# rys_PCB.net
KiCad netlist of a schematic drawn in Altium Designer
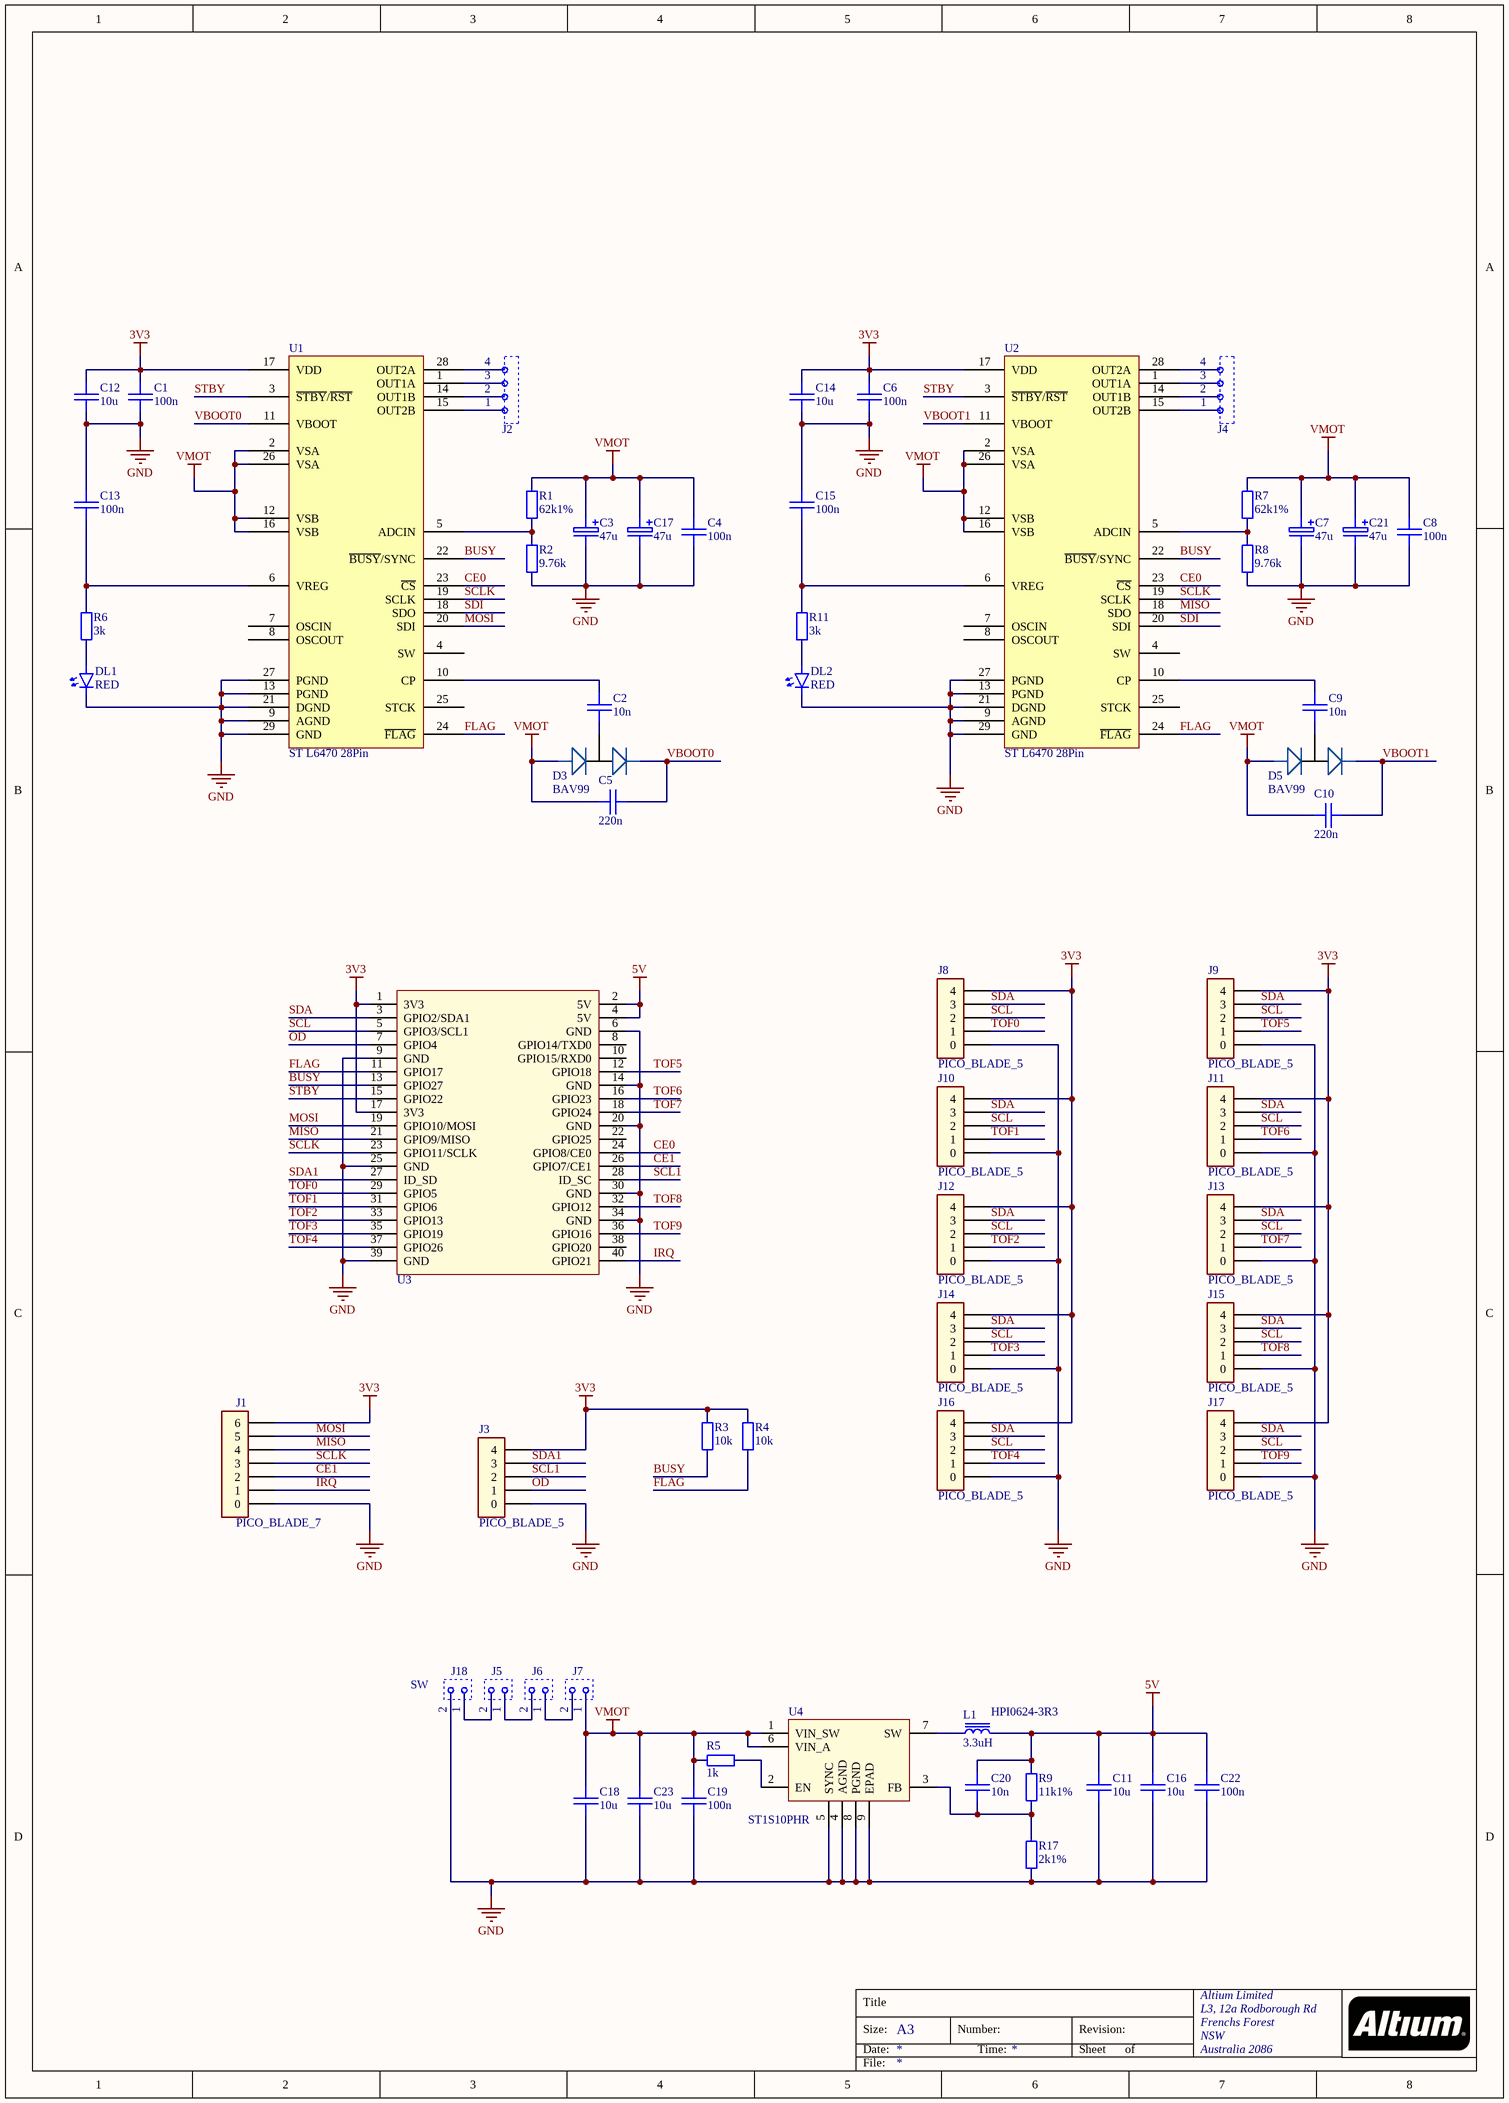
[diagram p0: rys_PCB.SchDoc]

(export (version "E")
  (design (tool "Eeschema 10.0.6"))
  (components
    (comp (ref "C1")
      (value "100n")
      (footprint "Other-Discrete:0603")
      (description "Ceramic Capacitor")
      (libsource (lib "Disc-Other") (part "C_CER"))
    )
    (comp (ref "C2")
      (value "10n")
      (footprint "Other-Discrete:0603")
      (description "Ceramic Capacitor")
      (libsource (lib "Disc-Other") (part "C_CER"))
    )
    (comp (ref "C3")
      (value "47u")
      (footprint "_C_TAN_D")
      (description "Tantalum Capacitor")
      (libsource (lib "Disc-Other") (part "C_TAN"))
    )
    (comp (ref "C4")
      (value "100n")
      (footprint "Other-Discrete:0603")
      (description "Ceramic Capacitor")
      (libsource (lib "Disc-Other") (part "C_CER"))
    )
    (comp (ref "C5")
      (value "220n")
      (footprint "Other-Discrete:0805")
      (description "Ceramic Capacitor")
      (libsource (lib "Disc-Other") (part "C_CER"))
    )
    (comp (ref "C6")
      (value "100n")
      (footprint "Other-Discrete:0603")
      (description "Ceramic Capacitor")
      (libsource (lib "Disc-Other") (part "C_CER"))
    )
    (comp (ref "C7")
      (value "47u")
      (footprint "_C_TAN_D")
      (description "Tantalum Capacitor")
      (libsource (lib "Disc-Other") (part "C_TAN"))
    )
    (comp (ref "C8")
      (value "100n")
      (footprint "Other-Discrete:0603")
      (description "Ceramic Capacitor")
      (libsource (lib "Disc-Other") (part "C_CER"))
    )
    (comp (ref "C9")
      (value "10n")
      (footprint "Other-Discrete:0603")
      (description "Ceramic Capacitor")
      (libsource (lib "Disc-Other") (part "C_CER"))
    )
    (comp (ref "C10")
      (value "220n")
      (footprint "Other-Discrete:0805")
      (description "Ceramic Capacitor")
      (libsource (lib "Disc-Other") (part "C_CER"))
    )
    (comp (ref "C11")
      (value "10u")
      (footprint "Other-Discrete:1210_C")
      (description "Ceramic Capacitor")
      (libsource (lib "Disc-Other") (part "C_CER"))
    )
    (comp (ref "C12")
      (value "10u")
      (footprint "Other-Discrete:1206_C")
      (description "Ceramic Capacitor")
      (libsource (lib "Disc-Other") (part "C_CER"))
    )
    (comp (ref "C13")
      (value "100n")
      (footprint "Other-Discrete:0603")
      (description "Ceramic Capacitor")
      (libsource (lib "Disc-Other") (part "C_CER"))
    )
    (comp (ref "C14")
      (value "10u")
      (footprint "Other-Discrete:1206_C")
      (description "Ceramic Capacitor")
      (libsource (lib "Disc-Other") (part "C_CER"))
    )
    (comp (ref "C15")
      (value "100n")
      (footprint "Other-Discrete:0603")
      (description "Ceramic Capacitor")
      (libsource (lib "Disc-Other") (part "C_CER"))
    )
    (comp (ref "C16")
      (value "10u")
      (footprint "Other-Discrete:1210_C")
      (description "Ceramic Capacitor")
      (libsource (lib "Disc-Other") (part "C_CER"))
    )
    (comp (ref "C17")
      (value "47u")
      (footprint "_C_TAN_D")
      (description "Tantalum Capacitor")
      (libsource (lib "Disc-Other") (part "C_TAN"))
    )
    (comp (ref "C18")
      (value "10u")
      (footprint "Other-Discrete:1210_C")
      (description "Ceramic Capacitor")
      (libsource (lib "Disc-Other") (part "C_CER"))
    )
    (comp (ref "C19")
      (value "100n")
      (footprint "Other-Discrete:0603")
      (description "Ceramic Capacitor")
      (libsource (lib "Disc-Other") (part "C_CER"))
    )
    (comp (ref "C20")
      (value "10n")
      (footprint "Other-Discrete:0603")
      (description "Ceramic Capacitor")
      (libsource (lib "Disc-Other") (part "C_CER"))
    )
    (comp (ref "C21")
      (value "47u")
      (footprint "_C_TAN_D")
      (description "Tantalum Capacitor")
      (libsource (lib "Disc-Other") (part "C_TAN"))
    )
    (comp (ref "C22")
      (value "100n")
      (footprint "Other-Discrete:0603")
      (description "Ceramic Capacitor")
      (libsource (lib "Disc-Other") (part "C_CER"))
    )
    (comp (ref "C23")
      (value "10u")
      (footprint "Other-Discrete:1210_C")
      (description "Ceramic Capacitor")
      (libsource (lib "Disc-Other") (part "C_CER"))
    )
    (comp (ref "D3")
      (value "BAV99")
      (footprint "SOT-23")
      (description "Charge pump diode")
      (libsource (lib "rys_component_lib") (part "BAV99"))
    )
    (comp (ref "D5")
      (value "BAV99")
      (footprint "SOT-23")
      (description "Charge pump diode")
      (libsource (lib "rys_component_lib") (part "BAV99"))
    )
    (comp (ref "DL1")
      (value "RED")
      (footprint "Other-Discrete:0805_LED")
      (description "Light Emitting Diode")
      (libsource (lib "Disc-Opto") (part "LED1"))
    )
    (comp (ref "DL2")
      (value "RED")
      (footprint "Other-Discrete:0805_LED")
      (description "Light Emitting Diode")
      (libsource (lib "Disc-Opto") (part "LED1"))
    )
    (comp (ref "J1")
      (value "PICO_BLADE_7")
      (footprint "PicoBlade_THT_1x7_HEADER")
      (description "1x7 header")
      (libsource (lib "rys_component_lib") (part "PICO_BLADE_7"))
    )
    (comp (ref "J2")
      (value "Molex Microfit")
      (footprint "MICROFIT 4x1 Vertical")
      (libsource (lib "rys_component_lib") (part "Microfit 1x4"))
    )
    (comp (ref "J3")
      (value "PICO_BLADE_5")
      (footprint "PicoBlade_THT_1x5_HEADER")
      (description "1x5 header")
      (libsource (lib "rys_component_lib") (part "PICO_BLADE_5"))
    )
    (comp (ref "J4")
      (value "Molex Microfit")
      (footprint "MICROFIT 4x1 Vertical")
      (libsource (lib "rys_component_lib") (part "Microfit 1x4"))
    )
    (comp (ref "J5")
      (value "Molex Microfit")
      (footprint "MicroFit:MICROFIT 1x2 Vertical")
      (libsource (lib "Connectors") (part "Microfit 2x1"))
    )
    (comp (ref "J6")
      (value "Molex Microfit")
      (footprint "MicroFit:MICROFIT 1x2 Vertical")
      (libsource (lib "Connectors") (part "Microfit 2x1"))
    )
    (comp (ref "J7")
      (value "Molex Microfit")
      (footprint "MicroFit:MICROFIT 1x2 Vertical")
      (libsource (lib "Connectors") (part "Microfit 2x1"))
    )
    (comp (ref "J8")
      (value "PICO_BLADE_5")
      (footprint "PicoBlade_THT_1x5_HEADER")
      (description "1x5 header")
      (libsource (lib "rys_component_lib") (part "PICO_BLADE_5"))
    )
    (comp (ref "J9")
      (value "PICO_BLADE_5")
      (footprint "PicoBlade_THT_1x5_HEADER")
      (description "1x5 header")
      (libsource (lib "rys_component_lib") (part "PICO_BLADE_5"))
    )
    (comp (ref "J10")
      (value "PICO_BLADE_5")
      (footprint "PicoBlade_THT_1x5_HEADER")
      (description "1x5 header")
      (libsource (lib "rys_component_lib") (part "PICO_BLADE_5"))
    )
    (comp (ref "J11")
      (value "PICO_BLADE_5")
      (footprint "PicoBlade_THT_1x5_HEADER")
      (description "1x5 header")
      (libsource (lib "rys_component_lib") (part "PICO_BLADE_5"))
    )
    (comp (ref "J12")
      (value "PICO_BLADE_5")
      (footprint "PicoBlade_THT_1x5_HEADER")
      (description "1x5 header")
      (libsource (lib "rys_component_lib") (part "PICO_BLADE_5"))
    )
    (comp (ref "J13")
      (value "PICO_BLADE_5")
      (footprint "PicoBlade_THT_1x5_HEADER")
      (description "1x5 header")
      (libsource (lib "rys_component_lib") (part "PICO_BLADE_5"))
    )
    (comp (ref "J14")
      (value "PICO_BLADE_5")
      (footprint "PicoBlade_THT_1x5_HEADER")
      (description "1x5 header")
      (libsource (lib "rys_component_lib") (part "PICO_BLADE_5"))
    )
    (comp (ref "J15")
      (value "PICO_BLADE_5")
      (footprint "PicoBlade_THT_1x5_HEADER")
      (description "1x5 header")
      (libsource (lib "rys_component_lib") (part "PICO_BLADE_5"))
    )
    (comp (ref "J16")
      (value "PICO_BLADE_5")
      (footprint "PicoBlade_THT_1x5_HEADER")
      (description "1x5 header")
      (libsource (lib "rys_component_lib") (part "PICO_BLADE_5"))
    )
    (comp (ref "J17")
      (value "PICO_BLADE_5")
      (footprint "PicoBlade_THT_1x5_HEADER")
      (description "1x5 header")
      (libsource (lib "rys_component_lib") (part "PICO_BLADE_5"))
    )
    (comp (ref "J18")
      (value "Molex Microfit")
      (footprint "MicroFit:MICROFIT 1x2 Vertical")
      (libsource (lib "Connectors") (part "Microfit 2x1"))
    )
    (comp (ref "L1")
      (value "3.3uH")
      (footprint "L_HPI0624")
      (description "Inductor")
      (fields (field (name "SYMBOL") "HPI0624-3R3"))
      (libsource (lib "rys_component_lib") (part "L_IND_HPI0624-3R3"))
    )
    (comp (ref "R1")
      (value "62k1%")
      (footprint "Other-Discrete:0603_R")
      (description "Resistor")
      (libsource (lib "Disc-Other") (part "R"))
    )
    (comp (ref "R2")
      (value "9.76k")
      (footprint "Other-Discrete:0603_R")
      (description "Resistor")
      (libsource (lib "Disc-Other") (part "R"))
    )
    (comp (ref "R3")
      (value "10k")
      (footprint "Other-Discrete:0603_R")
      (description "Resistor")
      (libsource (lib "Disc-Other") (part "R"))
    )
    (comp (ref "R4")
      (value "10k")
      (footprint "Other-Discrete:0603_R")
      (description "Resistor")
      (libsource (lib "Disc-Other") (part "R"))
    )
    (comp (ref "R5")
      (value "1k")
      (footprint "Other-Discrete:0603_R")
      (description "Resistor")
      (libsource (lib "Disc-Other") (part "R"))
    )
    (comp (ref "R6")
      (value "3k")
      (footprint "Other-Discrete:0603_R")
      (description "Resistor")
      (libsource (lib "Disc-Other") (part "R"))
    )
    (comp (ref "R7")
      (value "62k1%")
      (footprint "Other-Discrete:0603_R")
      (description "Resistor")
      (libsource (lib "Disc-Other") (part "R"))
    )
    (comp (ref "R8")
      (value "9.76k")
      (footprint "Other-Discrete:0603_R")
      (description "Resistor")
      (libsource (lib "Disc-Other") (part "R"))
    )
    (comp (ref "R9")
      (value "11k1%")
      (footprint "Other-Discrete:0603_R")
      (description "Resistor")
      (libsource (lib "Disc-Other") (part "R"))
    )
    (comp (ref "R11")
      (value "3k")
      (footprint "Other-Discrete:0603_R")
      (description "Resistor")
      (libsource (lib "Disc-Other") (part "R"))
    )
    (comp (ref "R17")
      (value "2k1%")
      (footprint "Other-Discrete:0603_R")
      (description "Resistor")
      (libsource (lib "Disc-Other") (part "R"))
    )
    (comp (ref "U1")
      (value "ST L6470 28Pin")
      (footprint "ST HTSSOP-28")
      (description "SPI stepper driver")
      (libsource (lib "rys_component_lib") (part "ST L6470 28Pin"))
    )
    (comp (ref "U2")
      (value "ST L6470 28Pin")
      (footprint "ST HTSSOP-28")
      (description "SPI stepper driver")
      (libsource (lib "rys_component_lib") (part "ST L6470 28Pin"))
    )
    (comp (ref "U3")
      (value "RaspberryPi_3B+")
      (footprint "RaspberryPi_S")
      (libsource (lib "rys_component_lib") (part "RaspberryPi_3B+"))
    )
    (comp (ref "U4")
      (value "ST1S10PHR")
      (footprint "HSOP8")
      (description "DC/DC converter 3A")
      (libsource (lib "rys_component_lib") (part "ST1S10PHR"))
    )
  )
  (nets
    (net (code "1") (name "/BUSY") (class "Default")
      (node (ref "R3") (pin "1") (pinfunction "1_1") (pintype "passive"))
      (node (ref "U1") (pin "22") (pinfunction "~{BUSY}/SYNC_22") (pintype "passive"))
      (node (ref "U2") (pin "22") (pinfunction "~{BUSY}/SYNC_22") (pintype "passive"))
      (node (ref "U3") (pin "13") (pinfunction "GPIO27_13") (pintype "passive"))
    )
    (net (code "2") (name "/CE0") (class "Default")
      (node (ref "U1") (pin "23") (pinfunction "~{CS}_23") (pintype "passive"))
      (node (ref "U2") (pin "23") (pinfunction "~{CS}_23") (pintype "passive"))
      (node (ref "U3") (pin "24") (pinfunction "GPIO8/CE0_24") (pintype "passive"))
    )
    (net (code "3") (name "/CE1") (class "Default")
      (node (ref "J1") (pin "2") (pinfunction "2_2") (pintype "passive"))
      (node (ref "U3") (pin "26") (pinfunction "GPIO7/CE1_26") (pintype "passive"))
    )
    (net (code "4") (name "/FLAG") (class "Default")
      (node (ref "R4") (pin "1") (pinfunction "1_1") (pintype "passive"))
      (node (ref "U1") (pin "24") (pinfunction "~{FLAG}_24") (pintype "passive"))
      (node (ref "U2") (pin "24") (pinfunction "~{FLAG}_24") (pintype "passive"))
      (node (ref "U3") (pin "11") (pinfunction "GPIO17_11") (pintype "passive"))
    )
    (net (code "5") (name "/IRQ") (class "Default")
      (node (ref "J1") (pin "1") (pinfunction "1_1") (pintype "passive"))
      (node (ref "U3") (pin "40") (pinfunction "GPIO21_40") (pintype "passive"))
    )
    (net (code "6") (name "/MISO") (class "Default")
      (node (ref "J1") (pin "4") (pinfunction "4_4") (pintype "passive"))
      (node (ref "U2") (pin "18") (pinfunction "SDO_18") (pintype "passive"))
      (node (ref "U3") (pin "21") (pinfunction "GPIO9/MISO_21") (pintype "passive"))
    )
    (net (code "7") (name "/MOSI") (class "Default")
      (node (ref "J1") (pin "5") (pinfunction "5_5") (pintype "passive"))
      (node (ref "U1") (pin "20") (pinfunction "SDI_20") (pintype "passive"))
      (node (ref "U3") (pin "19") (pinfunction "GPIO10/MOSI_19") (pintype "passive"))
    )
    (net (code "8") (name "/O~{D}") (class "Default")
      (node (ref "J3") (pin "1") (pinfunction "1_1") (pintype "passive"))
      (node (ref "U3") (pin "7") (pinfunction "GPIO4_7") (pintype "passive"))
    )
    (net (code "9") (name "/SCL") (class "Default")
      (node (ref "J10") (pin "2") (pinfunction "2_2") (pintype "passive"))
      (node (ref "J11") (pin "2") (pinfunction "2_2") (pintype "passive"))
      (node (ref "J12") (pin "2") (pinfunction "2_2") (pintype "passive"))
      (node (ref "J13") (pin "2") (pinfunction "2_2") (pintype "passive"))
      (node (ref "J14") (pin "2") (pinfunction "2_2") (pintype "passive"))
      (node (ref "J15") (pin "2") (pinfunction "2_2") (pintype "passive"))
      (node (ref "J16") (pin "2") (pinfunction "2_2") (pintype "passive"))
      (node (ref "J17") (pin "2") (pinfunction "2_2") (pintype "passive"))
      (node (ref "J8") (pin "2") (pinfunction "2_2") (pintype "passive"))
      (node (ref "J9") (pin "2") (pinfunction "2_2") (pintype "passive"))
      (node (ref "U3") (pin "5") (pinfunction "GPIO3/SCL1_5") (pintype "passive"))
    )
    (net (code "10") (name "/SCL1") (class "Default")
      (node (ref "J3") (pin "2") (pinfunction "2_2") (pintype "passive"))
      (node (ref "U3") (pin "28") (pinfunction "ID_SC_28") (pintype "passive"))
    )
    (net (code "11") (name "/SCLK") (class "Default")
      (node (ref "J1") (pin "3") (pinfunction "3_3") (pintype "passive"))
      (node (ref "U1") (pin "19") (pinfunction "SCLK_19") (pintype "passive"))
      (node (ref "U2") (pin "19") (pinfunction "SCLK_19") (pintype "passive"))
      (node (ref "U3") (pin "23") (pinfunction "GPIO11/SCLK_23") (pintype "passive"))
    )
    (net (code "12") (name "/SDA") (class "Default")
      (node (ref "J10") (pin "3") (pinfunction "3_3") (pintype "passive"))
      (node (ref "J11") (pin "3") (pinfunction "3_3") (pintype "passive"))
      (node (ref "J12") (pin "3") (pinfunction "3_3") (pintype "passive"))
      (node (ref "J13") (pin "3") (pinfunction "3_3") (pintype "passive"))
      (node (ref "J14") (pin "3") (pinfunction "3_3") (pintype "passive"))
      (node (ref "J15") (pin "3") (pinfunction "3_3") (pintype "passive"))
      (node (ref "J16") (pin "3") (pinfunction "3_3") (pintype "passive"))
      (node (ref "J17") (pin "3") (pinfunction "3_3") (pintype "passive"))
      (node (ref "J8") (pin "3") (pinfunction "3_3") (pintype "passive"))
      (node (ref "J9") (pin "3") (pinfunction "3_3") (pintype "passive"))
      (node (ref "U3") (pin "3") (pinfunction "GPIO2/SDA1_3") (pintype "passive"))
    )
    (net (code "13") (name "/SDA1") (class "Default")
      (node (ref "J3") (pin "3") (pinfunction "3_3") (pintype "passive"))
      (node (ref "U3") (pin "27") (pinfunction "ID_SD_27") (pintype "passive"))
    )
    (net (code "14") (name "/SDI") (class "Default")
      (node (ref "U1") (pin "18") (pinfunction "SDO_18") (pintype "passive"))
      (node (ref "U2") (pin "20") (pinfunction "SDI_20") (pintype "passive"))
    )
    (net (code "15") (name "/STBY") (class "Default")
      (node (ref "U1") (pin "3") (pinfunction "~{STBY}/~{RST}_3") (pintype "passive"))
      (node (ref "U2") (pin "3") (pinfunction "~{STBY}/~{RST}_3") (pintype "passive"))
      (node (ref "U3") (pin "15") (pinfunction "GPIO22_15") (pintype "passive"))
    )
    (net (code "16") (name "/TOF0") (class "Default")
      (node (ref "J8") (pin "1") (pinfunction "1_1") (pintype "passive"))
      (node (ref "U3") (pin "29") (pinfunction "GPIO5_29") (pintype "passive"))
    )
    (net (code "17") (name "/TOF1") (class "Default")
      (node (ref "J10") (pin "1") (pinfunction "1_1") (pintype "passive"))
      (node (ref "U3") (pin "31") (pinfunction "GPIO6_31") (pintype "passive"))
    )
    (net (code "18") (name "/TOF2") (class "Default")
      (node (ref "J12") (pin "1") (pinfunction "1_1") (pintype "passive"))
      (node (ref "U3") (pin "33") (pinfunction "GPIO13_33") (pintype "passive"))
    )
    (net (code "19") (name "/TOF3") (class "Default")
      (node (ref "J14") (pin "1") (pinfunction "1_1") (pintype "passive"))
      (node (ref "U3") (pin "35") (pinfunction "GPIO19_35") (pintype "passive"))
    )
    (net (code "20") (name "/TOF4") (class "Default")
      (node (ref "J16") (pin "1") (pinfunction "1_1") (pintype "passive"))
      (node (ref "U3") (pin "37") (pinfunction "GPIO26_37") (pintype "passive"))
    )
    (net (code "21") (name "/TOF5") (class "Default")
      (node (ref "J9") (pin "1") (pinfunction "1_1") (pintype "passive"))
      (node (ref "U3") (pin "12") (pinfunction "GPIO18_12") (pintype "passive"))
    )
    (net (code "22") (name "/TOF6") (class "Default")
      (node (ref "J11") (pin "1") (pinfunction "1_1") (pintype "passive"))
      (node (ref "U3") (pin "16") (pinfunction "GPIO23_16") (pintype "passive"))
    )
    (net (code "23") (name "/TOF7") (class "Default")
      (node (ref "J13") (pin "1") (pinfunction "1_1") (pintype "passive"))
      (node (ref "U3") (pin "18") (pinfunction "GPIO24_18") (pintype "passive"))
    )
    (net (code "24") (name "/TOF8") (class "Default")
      (node (ref "J15") (pin "1") (pinfunction "1_1") (pintype "passive"))
      (node (ref "U3") (pin "32") (pinfunction "GPIO12_32") (pintype "passive"))
    )
    (net (code "25") (name "/TOF9") (class "Default")
      (node (ref "J17") (pin "1") (pinfunction "1_1") (pintype "passive"))
      (node (ref "U3") (pin "36") (pinfunction "GPIO16_36") (pintype "passive"))
    )
    (net (code "26") (name "/VBOOT0") (class "Default")
      (node (ref "C5") (pin "1") (pinfunction "1_1") (pintype "passive"))
      (node (ref "D3") (pin "2") (pinfunction "2_2") (pintype "passive"))
      (node (ref "U1") (pin "11") (pinfunction "VBOOT_11") (pintype "passive"))
    )
    (net (code "27") (name "/VBOOT1") (class "Default")
      (node (ref "C10") (pin "1") (pinfunction "1_1") (pintype "passive"))
      (node (ref "D5") (pin "2") (pinfunction "2_2") (pintype "passive"))
      (node (ref "U2") (pin "11") (pinfunction "VBOOT_11") (pintype "passive"))
    )
    (net (code "28") (name "3V3") (class "Default")
      (node (ref "C1") (pin "2") (pinfunction "2_2") (pintype "passive"))
      (node (ref "C12") (pin "2") (pinfunction "2_2") (pintype "passive"))
      (node (ref "C14") (pin "2") (pinfunction "2_2") (pintype "passive"))
      (node (ref "C6") (pin "2") (pinfunction "2_2") (pintype "passive"))
      (node (ref "J1") (pin "6") (pinfunction "6_6") (pintype "passive"))
      (node (ref "J10") (pin "4") (pinfunction "4_4") (pintype "passive"))
      (node (ref "J11") (pin "4") (pinfunction "4_4") (pintype "passive"))
      (node (ref "J12") (pin "4") (pinfunction "4_4") (pintype "passive"))
      (node (ref "J13") (pin "4") (pinfunction "4_4") (pintype "passive"))
      (node (ref "J14") (pin "4") (pinfunction "4_4") (pintype "passive"))
      (node (ref "J15") (pin "4") (pinfunction "4_4") (pintype "passive"))
      (node (ref "J16") (pin "4") (pinfunction "4_4") (pintype "passive"))
      (node (ref "J17") (pin "4") (pinfunction "4_4") (pintype "passive"))
      (node (ref "J3") (pin "4") (pinfunction "4_4") (pintype "passive"))
      (node (ref "J8") (pin "4") (pinfunction "4_4") (pintype "passive"))
      (node (ref "J9") (pin "4") (pinfunction "4_4") (pintype "passive"))
      (node (ref "R3") (pin "2") (pinfunction "2_2") (pintype "passive"))
      (node (ref "R4") (pin "2") (pinfunction "2_2") (pintype "passive"))
      (node (ref "U1") (pin "17") (pinfunction "VDD_17") (pintype "passive"))
      (node (ref "U2") (pin "17") (pinfunction "VDD_17") (pintype "passive"))
      (node (ref "U3") (pin "1") (pinfunction "3V3_1") (pintype "passive"))
      (node (ref "U3") (pin "17") (pinfunction "3V3_17") (pintype "passive"))
    )
    (net (code "29") (name "5V") (class "Default")
      (node (ref "C11") (pin "2") (pinfunction "2_2") (pintype "passive"))
      (node (ref "C16") (pin "2") (pinfunction "2_2") (pintype "passive"))
      (node (ref "C20") (pin "2") (pinfunction "2_2") (pintype "passive"))
      (node (ref "C22") (pin "2") (pinfunction "2_2") (pintype "passive"))
      (node (ref "L1") (pin "1") (pinfunction "1_1") (pintype "passive"))
      (node (ref "R9") (pin "2") (pinfunction "2_2") (pintype "passive"))
      (node (ref "U3") (pin "2") (pinfunction "5V_2") (pintype "passive"))
      (node (ref "U3") (pin "4") (pinfunction "5V_4") (pintype "passive"))
    )
    (net (code "30") (name "GND") (class "Default")
      (node (ref "C1") (pin "1") (pinfunction "1_1") (pintype "passive"))
      (node (ref "C11") (pin "1") (pinfunction "1_1") (pintype "passive"))
      (node (ref "C12") (pin "1") (pinfunction "1_1") (pintype "passive"))
      (node (ref "C13") (pin "2") (pinfunction "2_2") (pintype "passive"))
      (node (ref "C14") (pin "1") (pinfunction "1_1") (pintype "passive"))
      (node (ref "C15") (pin "2") (pinfunction "2_2") (pintype "passive"))
      (node (ref "C16") (pin "1") (pinfunction "1_1") (pintype "passive"))
      (node (ref "C17") (pin "N") (pinfunction "2_N") (pintype "passive"))
      (node (ref "C18") (pin "1") (pinfunction "1_1") (pintype "passive"))
      (node (ref "C19") (pin "1") (pinfunction "1_1") (pintype "passive"))
      (node (ref "C21") (pin "N") (pinfunction "2_N") (pintype "passive"))
      (node (ref "C22") (pin "1") (pinfunction "1_1") (pintype "passive"))
      (node (ref "C23") (pin "1") (pinfunction "1_1") (pintype "passive"))
      (node (ref "C3") (pin "N") (pinfunction "2_N") (pintype "passive"))
      (node (ref "C4") (pin "2") (pinfunction "2_2") (pintype "passive"))
      (node (ref "C6") (pin "1") (pinfunction "1_1") (pintype "passive"))
      (node (ref "C7") (pin "N") (pinfunction "2_N") (pintype "passive"))
      (node (ref "C8") (pin "2") (pinfunction "2_2") (pintype "passive"))
      (node (ref "DL1") (pin "K") (pinfunction "1_K") (pintype "passive"))
      (node (ref "DL2") (pin "K") (pinfunction "1_K") (pintype "passive"))
      (node (ref "J1") (pin "0") (pinfunction "0_0") (pintype "passive"))
      (node (ref "J10") (pin "0") (pinfunction "0_0") (pintype "passive"))
      (node (ref "J11") (pin "0") (pinfunction "0_0") (pintype "passive"))
      (node (ref "J12") (pin "0") (pinfunction "0_0") (pintype "passive"))
      (node (ref "J13") (pin "0") (pinfunction "0_0") (pintype "passive"))
      (node (ref "J14") (pin "0") (pinfunction "0_0") (pintype "passive"))
      (node (ref "J15") (pin "0") (pinfunction "0_0") (pintype "passive"))
      (node (ref "J16") (pin "0") (pinfunction "0_0") (pintype "passive"))
      (node (ref "J17") (pin "0") (pinfunction "0_0") (pintype "passive"))
      (node (ref "J18") (pin "2") (pintype "passive"))
      (node (ref "J3") (pin "0") (pinfunction "0_0") (pintype "passive"))
      (node (ref "J8") (pin "0") (pinfunction "0_0") (pintype "passive"))
      (node (ref "J9") (pin "0") (pinfunction "0_0") (pintype "passive"))
      (node (ref "R17") (pin "1") (pinfunction "1_1") (pintype "passive"))
      (node (ref "R2") (pin "1") (pinfunction "1_1") (pintype "passive"))
      (node (ref "R8") (pin "1") (pinfunction "1_1") (pintype "passive"))
      (node (ref "U1") (pin "13") (pinfunction "PGND_13") (pintype "passive"))
      (node (ref "U1") (pin "21") (pinfunction "DGND_21") (pintype "passive"))
      (node (ref "U1") (pin "27") (pinfunction "PGND_27") (pintype "passive"))
      (node (ref "U1") (pin "29") (pinfunction "GND_29") (pintype "passive"))
      (node (ref "U1") (pin "9") (pinfunction "AGND_9") (pintype "passive"))
      (node (ref "U2") (pin "13") (pinfunction "PGND_13") (pintype "passive"))
      (node (ref "U2") (pin "21") (pinfunction "DGND_21") (pintype "passive"))
      (node (ref "U2") (pin "27") (pinfunction "PGND_27") (pintype "passive"))
      (node (ref "U2") (pin "29") (pinfunction "GND_29") (pintype "passive"))
      (node (ref "U2") (pin "9") (pinfunction "AGND_9") (pintype "passive"))
      (node (ref "U3") (pin "14") (pinfunction "GND_14") (pintype "passive"))
      (node (ref "U3") (pin "20") (pinfunction "GND_20") (pintype "passive"))
      (node (ref "U3") (pin "25") (pinfunction "GND_25") (pintype "passive"))
      (node (ref "U3") (pin "30") (pinfunction "GND_30") (pintype "passive"))
      (node (ref "U3") (pin "34") (pinfunction "GND_34") (pintype "passive"))
      (node (ref "U3") (pin "39") (pinfunction "GND_39") (pintype "passive"))
      (node (ref "U3") (pin "6") (pinfunction "GND_6") (pintype "passive"))
      (node (ref "U3") (pin "9") (pinfunction "GND_9") (pintype "passive"))
      (node (ref "U4") (pin "4") (pinfunction "AGND_4") (pintype "passive"))
      (node (ref "U4") (pin "5") (pinfunction "SYNC_5") (pintype "passive"))
      (node (ref "U4") (pin "8") (pinfunction "PGND_8") (pintype "passive"))
      (node (ref "U4") (pin "9") (pinfunction "EPAD_9") (pintype "passive"))
    )
    (net (code "31") (name "Net-(C2-Pad1)") (class "Default")
      (node (ref "C2") (pin "1") (pinfunction "1_1") (pintype "passive"))
      (node (ref "D3") (pin "3") (pinfunction "3_3") (pintype "passive"))
    )
    (net (code "32") (name "Net-(C9-Pad1)") (class "Default")
      (node (ref "C9") (pin "1") (pinfunction "1_1") (pintype "passive"))
      (node (ref "D5") (pin "3") (pinfunction "3_3") (pintype "passive"))
    )
    (net (code "33") (name "Net-(DL1-2)") (class "Default")
      (node (ref "DL1") (pin "A") (pinfunction "2_A") (pintype "passive"))
      (node (ref "R6") (pin "1") (pinfunction "1_1") (pintype "passive"))
    )
    (net (code "34") (name "Net-(DL2-2)") (class "Default")
      (node (ref "DL2") (pin "A") (pinfunction "2_A") (pintype "passive"))
      (node (ref "R11") (pin "1") (pinfunction "1_1") (pintype "passive"))
    )
    (net (code "35") (name "Net-(J5-Pad1)") (class "Default")
      (node (ref "J5") (pin "1") (pintype "passive"))
      (node (ref "J6") (pin "2") (pintype "passive"))
    )
    (net (code "36") (name "Net-(J6-Pad1)") (class "Default")
      (node (ref "J6") (pin "1") (pintype "passive"))
      (node (ref "J7") (pin "2") (pintype "passive"))
    )
    (net (code "37") (name "Net-(J18-Pad1)") (class "Default")
      (node (ref "J18") (pin "1") (pintype "passive"))
      (node (ref "J5") (pin "2") (pintype "passive"))
    )
    (net (code "38") (name "Net-(U1-ADCIN)") (class "Default")
      (node (ref "R1") (pin "1") (pinfunction "1_1") (pintype "passive"))
      (node (ref "R2") (pin "2") (pinfunction "2_2") (pintype "passive"))
      (node (ref "U1") (pin "5") (pinfunction "ADCIN_5") (pintype "passive"))
    )
    (net (code "39") (name "Net-(U1-CP)") (class "Default")
      (node (ref "C2") (pin "2") (pinfunction "2_2") (pintype "passive"))
      (node (ref "U1") (pin "10") (pinfunction "CP_10") (pintype "passive"))
    )
    (net (code "40") (name "Net-(U1-OUT1A)") (class "Default")
      (node (ref "J2") (pin "3") (pintype "passive"))
      (node (ref "U1") (pin "1") (pinfunction "OUT1A_1") (pintype "passive"))
    )
    (net (code "41") (name "Net-(U1-OUT1B)") (class "Default")
      (node (ref "J2") (pin "2") (pintype "passive"))
      (node (ref "U1") (pin "14") (pinfunction "OUT1B_14") (pintype "passive"))
    )
    (net (code "42") (name "Net-(U1-OUT2A)") (class "Default")
      (node (ref "J2") (pin "4") (pintype "passive"))
      (node (ref "U1") (pin "28") (pinfunction "OUT2A_28") (pintype "passive"))
    )
    (net (code "43") (name "Net-(U1-OUT2B)") (class "Default")
      (node (ref "J2") (pin "1") (pintype "passive"))
      (node (ref "U1") (pin "15") (pinfunction "OUT2B_15") (pintype "passive"))
    )
    (net (code "44") (name "Net-(U1-VREG)") (class "Default")
      (node (ref "C13") (pin "1") (pinfunction "1_1") (pintype "passive"))
      (node (ref "R6") (pin "2") (pinfunction "2_2") (pintype "passive"))
      (node (ref "U1") (pin "6") (pinfunction "VREG_6") (pintype "passive"))
    )
    (net (code "45") (name "Net-(U2-ADCIN)") (class "Default")
      (node (ref "R7") (pin "1") (pinfunction "1_1") (pintype "passive"))
      (node (ref "R8") (pin "2") (pinfunction "2_2") (pintype "passive"))
      (node (ref "U2") (pin "5") (pinfunction "ADCIN_5") (pintype "passive"))
    )
    (net (code "46") (name "Net-(U2-CP)") (class "Default")
      (node (ref "C9") (pin "2") (pinfunction "2_2") (pintype "passive"))
      (node (ref "U2") (pin "10") (pinfunction "CP_10") (pintype "passive"))
    )
    (net (code "47") (name "Net-(U2-OUT1A)") (class "Default")
      (node (ref "J4") (pin "3") (pintype "passive"))
      (node (ref "U2") (pin "1") (pinfunction "OUT1A_1") (pintype "passive"))
    )
    (net (code "48") (name "Net-(U2-OUT1B)") (class "Default")
      (node (ref "J4") (pin "2") (pintype "passive"))
      (node (ref "U2") (pin "14") (pinfunction "OUT1B_14") (pintype "passive"))
    )
    (net (code "49") (name "Net-(U2-OUT2A)") (class "Default")
      (node (ref "J4") (pin "4") (pintype "passive"))
      (node (ref "U2") (pin "28") (pinfunction "OUT2A_28") (pintype "passive"))
    )
    (net (code "50") (name "Net-(U2-OUT2B)") (class "Default")
      (node (ref "J4") (pin "1") (pintype "passive"))
      (node (ref "U2") (pin "15") (pinfunction "OUT2B_15") (pintype "passive"))
    )
    (net (code "51") (name "Net-(U2-VREG)") (class "Default")
      (node (ref "C15") (pin "1") (pinfunction "1_1") (pintype "passive"))
      (node (ref "R11") (pin "2") (pinfunction "2_2") (pintype "passive"))
      (node (ref "U2") (pin "6") (pinfunction "VREG_6") (pintype "passive"))
    )
    (net (code "52") (name "Net-(U4-EN)") (class "Default")
      (node (ref "R5") (pin "1") (pinfunction "1_1") (pintype "passive"))
      (node (ref "U4") (pin "2") (pinfunction "EN_2") (pintype "passive"))
    )
    (net (code "53") (name "Net-(U4-FB)") (class "Default")
      (node (ref "C20") (pin "1") (pinfunction "1_1") (pintype "passive"))
      (node (ref "R17") (pin "2") (pinfunction "2_2") (pintype "passive"))
      (node (ref "R9") (pin "1") (pinfunction "1_1") (pintype "passive"))
      (node (ref "U4") (pin "3") (pinfunction "FB_3") (pintype "passive"))
    )
    (net (code "54") (name "Net-(U4-SW)") (class "Default")
      (node (ref "L1") (pin "2") (pinfunction "2_2") (pintype "passive"))
      (node (ref "U4") (pin "7") (pinfunction "SW_7") (pintype "passive"))
    )
    (net (code "55") (name "VMOT") (class "Default")
      (node (ref "C10") (pin "2") (pinfunction "2_2") (pintype "passive"))
      (node (ref "C17") (pin "P") (pinfunction "1_P") (pintype "passive"))
      (node (ref "C18") (pin "2") (pinfunction "2_2") (pintype "passive"))
      (node (ref "C19") (pin "2") (pinfunction "2_2") (pintype "passive"))
      (node (ref "C21") (pin "P") (pinfunction "1_P") (pintype "passive"))
      (node (ref "C23") (pin "2") (pinfunction "2_2") (pintype "passive"))
      (node (ref "C3") (pin "P") (pinfunction "1_P") (pintype "passive"))
      (node (ref "C4") (pin "1") (pinfunction "1_1") (pintype "passive"))
      (node (ref "C5") (pin "2") (pinfunction "2_2") (pintype "passive"))
      (node (ref "C7") (pin "P") (pinfunction "1_P") (pintype "passive"))
      (node (ref "C8") (pin "1") (pinfunction "1_1") (pintype "passive"))
      (node (ref "D3") (pin "1") (pinfunction "1_1") (pintype "passive"))
      (node (ref "D5") (pin "1") (pinfunction "1_1") (pintype "passive"))
      (node (ref "J7") (pin "1") (pintype "passive"))
      (node (ref "R1") (pin "2") (pinfunction "2_2") (pintype "passive"))
      (node (ref "R5") (pin "2") (pinfunction "2_2") (pintype "passive"))
      (node (ref "R7") (pin "2") (pinfunction "2_2") (pintype "passive"))
      (node (ref "U1") (pin "12") (pinfunction "VSB_12") (pintype "passive"))
      (node (ref "U1") (pin "16") (pinfunction "VSB_16") (pintype "passive"))
      (node (ref "U1") (pin "2") (pinfunction "VSA_2") (pintype "passive"))
      (node (ref "U1") (pin "26") (pinfunction "VSA_26") (pintype "passive"))
      (node (ref "U2") (pin "12") (pinfunction "VSB_12") (pintype "passive"))
      (node (ref "U2") (pin "16") (pinfunction "VSB_16") (pintype "passive"))
      (node (ref "U2") (pin "2") (pinfunction "VSA_2") (pintype "passive"))
      (node (ref "U2") (pin "26") (pinfunction "VSA_26") (pintype "passive"))
      (node (ref "U4") (pin "1") (pinfunction "VIN_SW_1") (pintype "passive"))
      (node (ref "U4") (pin "6") (pinfunction "VIN_A_6") (pintype "passive"))
    )
    (net (code "56") (name "unconnected-(U1-OSCIN-Pad7)") (class "Default")
      (node (ref "U1") (pin "7") (pinfunction "OSCIN_7") (pintype "passive"))
    )
    (net (code "57") (name "unconnected-(U1-OSCOUT-Pad8)") (class "Default")
      (node (ref "U1") (pin "8") (pinfunction "OSCOUT_8") (pintype "passive"))
    )
    (net (code "58") (name "unconnected-(U1-STCK-Pad25)") (class "Default")
      (node (ref "U1") (pin "25") (pinfunction "STCK_25") (pintype "passive"))
    )
    (net (code "59") (name "unconnected-(U1-SW-Pad4)") (class "Default")
      (node (ref "U1") (pin "4") (pinfunction "SW_4") (pintype "passive"))
    )
    (net (code "60") (name "unconnected-(U2-OSCIN-Pad7)") (class "Default")
      (node (ref "U2") (pin "7") (pinfunction "OSCIN_7") (pintype "passive"))
    )
    (net (code "61") (name "unconnected-(U2-OSCOUT-Pad8)") (class "Default")
      (node (ref "U2") (pin "8") (pinfunction "OSCOUT_8") (pintype "passive"))
    )
    (net (code "62") (name "unconnected-(U2-STCK-Pad25)") (class "Default")
      (node (ref "U2") (pin "25") (pinfunction "STCK_25") (pintype "passive"))
    )
    (net (code "63") (name "unconnected-(U2-SW-Pad4)") (class "Default")
      (node (ref "U2") (pin "4") (pinfunction "SW_4") (pintype "passive"))
    )
    (net (code "64") (name "unconnected-(U3-GPIO14{slash}TXD0-Pad8)") (class "Default")
      (node (ref "U3") (pin "8") (pinfunction "GPIO14/TXD0_8") (pintype "passive"))
    )
    (net (code "65") (name "unconnected-(U3-GPIO15{slash}RXD0-Pad10)") (class "Default")
      (node (ref "U3") (pin "10") (pinfunction "GPIO15/RXD0_10") (pintype "passive"))
    )
    (net (code "66") (name "unconnected-(U3-GPIO20-Pad38)") (class "Default")
      (node (ref "U3") (pin "38") (pinfunction "GPIO20_38") (pintype "passive"))
    )
    (net (code "67") (name "unconnected-(U3-GPIO25-Pad22)") (class "Default")
      (node (ref "U3") (pin "22") (pinfunction "GPIO25_22") (pintype "passive"))
    )
  )
)
